# Temperaturf_hler_V10_DLN18701.net
KiCad netlist of a schematic drawn in EAGLE
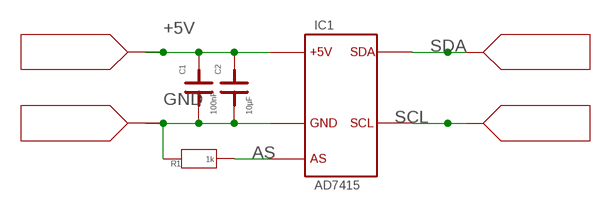
[diagram p0: schematic, sheet 1]

(export (version "E")
  (design (tool "Eeschema 10.0.6"))
  (components
    (comp (ref "C1")
      (value "100nF")
      (footprint "eagle-import:0805F")
      (libsource (lib "eagle-import") (part "C1"))
    )
    (comp (ref "C2")
      (value "10µF")
      (footprint "eagle-import:0805F")
      (libsource (lib "eagle-import") (part "C1"))
    )
    (comp (ref "IC1")
      (value "AD7415")
      (footprint "eagle-import:SOT23-5L")
      (libsource (lib "eagle-import") (part "AD7415"))
    )
    (comp (ref "LP1")
      (value "LP1")
      (footprint "eagle-import:LPS1")
      (libsource (lib "eagle-import") (part "LP1"))
    )
    (comp (ref "LP2")
      (value "LP1")
      (footprint "eagle-import:LPS1")
      (libsource (lib "eagle-import") (part "LP1"))
    )
    (comp (ref "LP3")
      (value "LP1")
      (footprint "eagle-import:LPS1")
      (libsource (lib "eagle-import") (part "LP1"))
    )
    (comp (ref "LP4")
      (value "LP1")
      (footprint "eagle-import:LPS1")
      (libsource (lib "eagle-import") (part "LP1"))
    )
    (comp (ref "R1")
      (value "1k")
      (footprint "eagle-import:0805")
      (libsource (lib "eagle-import") (part "R1"))
    )
  )
  (nets
    (net (code "1") (name "/+5V") (class "Default")
      (node (ref "C1") (pin "2") (pinfunction "2_2") (pintype "bidirectional"))
      (node (ref "C2") (pin "2") (pinfunction "2_2") (pintype "bidirectional"))
      (node (ref "IC1") (pin "3") (pinfunction "+5V_3") (pintype "bidirectional"))
      (node (ref "LP3") (pin "1") (pinfunction "1_1") (pintype "bidirectional"))
    )
    (net (code "2") (name "/AS") (class "Default")
      (node (ref "IC1") (pin "1") (pinfunction "AS_1") (pintype "bidirectional"))
      (node (ref "R1") (pin "1") (pinfunction "1_1") (pintype "bidirectional"))
    )
    (net (code "3") (name "/GND") (class "Default")
      (node (ref "C1") (pin "1") (pinfunction "1_1") (pintype "bidirectional"))
      (node (ref "C2") (pin "1") (pinfunction "1_1") (pintype "bidirectional"))
      (node (ref "IC1") (pin "2") (pinfunction "GND_2") (pintype "bidirectional"))
      (node (ref "LP4") (pin "1") (pinfunction "1_1") (pintype "bidirectional"))
      (node (ref "R1") (pin "2") (pinfunction "2_2") (pintype "bidirectional"))
    )
    (net (code "4") (name "/SCL") (class "Default")
      (node (ref "IC1") (pin "4") (pinfunction "SCL_4") (pintype "bidirectional"))
      (node (ref "LP2") (pin "1") (pinfunction "1_1") (pintype "bidirectional"))
    )
    (net (code "5") (name "/SDA") (class "Default")
      (node (ref "IC1") (pin "5") (pinfunction "SDA_5") (pintype "bidirectional"))
      (node (ref "LP1") (pin "1") (pinfunction "1_1") (pintype "bidirectional"))
    )
  )
)
